# SalinityExpansion.net
KiCad netlist of a schematic drawn in EAGLE
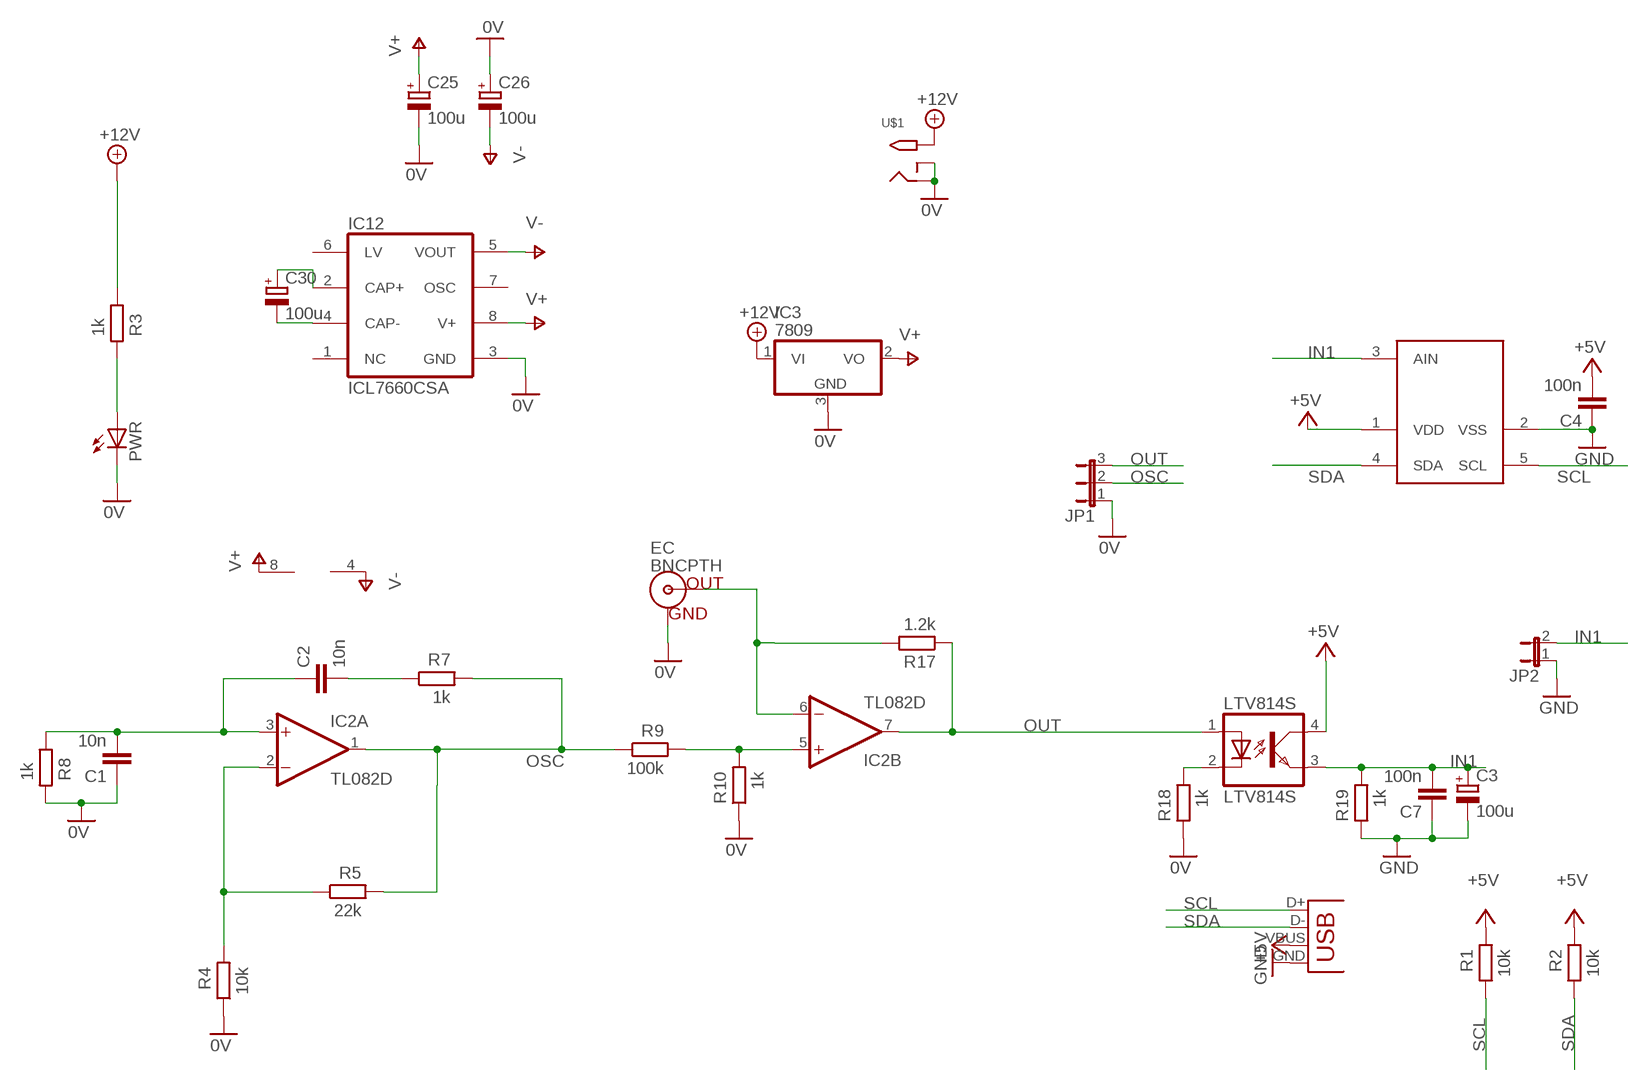
[diagram p0: schematic, sheet 1]

(export (version "E")
  (design (tool "Eeschema 10.0.6"))
  (components
    (comp (ref "C1")
      (value "10n")
      (footprint "eagle-import:C0805K")
      (libsource (lib "eagle-import") (part "C-EUC0805K"))
    )
    (comp (ref "C2")
      (value "10n")
      (footprint "eagle-import:C0805K")
      (libsource (lib "eagle-import") (part "C-EUC0805K"))
    )
    (comp (ref "C3")
      (value "100u")
      (footprint "eagle-import:PANASONIC_D")
      (libsource (lib "eagle-import") (part "CPOL-EUD"))
    )
    (comp (ref "C4")
      (value "100n")
      (footprint "eagle-import:C0805K")
      (libsource (lib "eagle-import") (part "C-EUC0805K"))
    )
    (comp (ref "C7")
      (value "100n")
      (footprint "eagle-import:C0805K")
      (libsource (lib "eagle-import") (part "C-EUC0805K"))
    )
    (comp (ref "C25")
      (value "100u")
      (footprint "eagle-import:PANASONIC_D")
      (libsource (lib "eagle-import") (part "CPOL-EUD"))
    )
    (comp (ref "C26")
      (value "100u")
      (footprint "eagle-import:PANASONIC_D")
      (libsource (lib "eagle-import") (part "CPOL-EUD"))
    )
    (comp (ref "C30")
      (value "100u")
      (footprint "eagle-import:PANASONIC_D")
      (libsource (lib "eagle-import") (part "CPOL-EUD"))
    )
    (comp (ref "EC")
      (value "BNCPTH")
      (footprint "eagle-import:BNC")
      (libsource (lib "eagle-import") (part "BNCPTH"))
    )
    (comp (ref "IC2")
      (value "TL082D")
      (footprint "eagle-import:SO08")
      (libsource (lib "eagle-import") (part "TL082D"))
    )
    (comp (ref "IC3")
      (value "7809")
      (footprint "eagle-import:TO252")
      (libsource (lib "eagle-import") (part "78DT05"))
    )
    (comp (ref "IC12")
      (value "ICL7660CSA")
      (footprint "eagle-import:SO08")
      (fields (field (name "MF") "MAXIM"))
      (libsource (lib "eagle-import") (part "ICL7660CSA"))
    )
    (comp (ref "JP1")
      (value "JP2E")
      (footprint "eagle-import:JP2")
      (libsource (lib "eagle-import") (part "JP2E"))
    )
    (comp (ref "JP2")
      (value "JP1E")
      (footprint "eagle-import:JP1")
      (libsource (lib "eagle-import") (part "JP1E"))
    )
    (comp (ref "LTV814S")
      (value "LTV814S")
      (footprint "eagle-import:SMD4")
      (libsource (lib "eagle-import") (part "LTV816S"))
    )
    (comp (ref "PWR")
      (value "LED3MM")
      (footprint "eagle-import:LED3MM")
      (libsource (lib "eagle-import") (part "LED3MM"))
    )
    (comp (ref "R1")
      (value "10k")
      (footprint "eagle-import:R0805")
      (libsource (lib "eagle-import") (part "R-EU_R0805"))
    )
    (comp (ref "R2")
      (value "10k")
      (footprint "eagle-import:R0805")
      (libsource (lib "eagle-import") (part "R-EU_R0805"))
    )
    (comp (ref "R3")
      (value "1k")
      (footprint "eagle-import:R0805")
      (libsource (lib "eagle-import") (part "R-EU_R0805"))
    )
    (comp (ref "R4")
      (value "10k")
      (footprint "eagle-import:R0805")
      (libsource (lib "eagle-import") (part "R-EU_R0805"))
    )
    (comp (ref "R5")
      (value "22k")
      (footprint "eagle-import:R0805")
      (libsource (lib "eagle-import") (part "R-EU_R0805"))
    )
    (comp (ref "R7")
      (value "1k")
      (footprint "eagle-import:R0805")
      (libsource (lib "eagle-import") (part "R-EU_R0805"))
    )
    (comp (ref "R8")
      (value "1k")
      (footprint "eagle-import:R0805")
      (libsource (lib "eagle-import") (part "R-EU_R0805"))
    )
    (comp (ref "R9")
      (value "100k")
      (footprint "eagle-import:R0805")
      (libsource (lib "eagle-import") (part "R-EU_R0805"))
    )
    (comp (ref "R10")
      (value "1k")
      (footprint "eagle-import:R0805")
      (libsource (lib "eagle-import") (part "R-EU_R0805"))
    )
    (comp (ref "R17")
      (value "1.2k")
      (footprint "eagle-import:R0805")
      (libsource (lib "eagle-import") (part "R-EU_R0805"))
    )
    (comp (ref "R18")
      (value "1k")
      (footprint "eagle-import:R0805")
      (libsource (lib "eagle-import") (part "R-EU_R0805"))
    )
    (comp (ref "R19")
      (value "1k")
      (footprint "eagle-import:R0805")
      (libsource (lib "eagle-import") (part "R-EU_R0805"))
    )
    (comp (ref "U$1")
      (value "2.1MMJACKTHM")
      (footprint "eagle-import:PJ-102A")
      (libsource (lib "eagle-import") (part "2.1MMJACKTHM"))
    )
    (comp (ref "U$2")
      (value "MCP3221")
      (footprint "eagle-import:SOT23-5")
      (libsource (lib "eagle-import") (part "MCP3221"))
    )
    (comp (ref "X5")
      (value "USBSMD")
      (footprint "eagle-import:USB-MINIB")
      (libsource (lib "eagle-import") (part "USBSMD"))
    )
  )
  (nets
    (net (code "1") (name "+5V") (class "Default")
      (node (ref "C4") (pin "2") (pinfunction "2_2") (pintype "passive"))
      (node (ref "LTV814S") (pin "4") (pinfunction "COL_4") (pintype "passive"))
      (node (ref "R1") (pin "2") (pinfunction "2_2") (pintype "passive"))
      (node (ref "R2") (pin "2") (pinfunction "2_2") (pintype "passive"))
      (node (ref "U$2") (pin "1") (pinfunction "VDD_1") (pintype "bidirectional"))
      (node (ref "X5") (pin "VBUS") (pinfunction "VBUS_VBUS") (pintype "bidirectional"))
    )
    (net (code "2") (name "+12V") (class "Default")
      (node (ref "IC3") (pin "1") (pinfunction "VI_1") (pintype "input"))
      (node (ref "R3") (pin "1") (pinfunction "1_1") (pintype "passive"))
      (node (ref "U$1") (pin "TIP") (pinfunction "TIP_TIP") (pintype "bidirectional"))
    )
    (net (code "3") (name "/IN1") (class "Default")
      (node (ref "C3") (pin "+") (pinfunction "+_+") (pintype "passive"))
      (node (ref "C7") (pin "2") (pinfunction "2_2") (pintype "passive"))
      (node (ref "JP2") (pin "2") (pinfunction "2_2") (pintype "passive"))
      (node (ref "LTV814S") (pin "3") (pinfunction "EMIT_3") (pintype "passive"))
      (node (ref "R19") (pin "2") (pinfunction "2_2") (pintype "passive"))
      (node (ref "U$2") (pin "3") (pinfunction "AIN_3") (pintype "bidirectional"))
    )
    (net (code "4") (name "/OSC") (class "Default")
      (node (ref "IC2") (pin "1") (pinfunction "OUT_1") (pintype "output"))
      (node (ref "JP1") (pin "2") (pinfunction "2_2") (pintype "passive"))
      (node (ref "R5") (pin "2") (pinfunction "2_2") (pintype "passive"))
      (node (ref "R7") (pin "2") (pinfunction "2_2") (pintype "passive"))
      (node (ref "R9") (pin "1") (pinfunction "1_1") (pintype "passive"))
    )
    (net (code "5") (name "/OUT") (class "Default")
      (node (ref "IC2") (pin "7") (pinfunction "OUT_7") (pintype "output"))
      (node (ref "JP1") (pin "3") (pinfunction "3_3") (pintype "passive"))
      (node (ref "LTV814S") (pin "1") (pinfunction "A_1") (pintype "passive"))
      (node (ref "R17") (pin "1") (pinfunction "1_1") (pintype "passive"))
    )
    (net (code "6") (name "/SCL") (class "Default")
      (node (ref "R1") (pin "1") (pinfunction "1_1") (pintype "passive"))
      (node (ref "U$2") (pin "5") (pinfunction "SCL_5") (pintype "bidirectional"))
      (node (ref "X5") (pin "D+") (pinfunction "D+_D+") (pintype "bidirectional"))
    )
    (net (code "7") (name "/SDA") (class "Default")
      (node (ref "R2") (pin "1") (pinfunction "1_1") (pintype "passive"))
      (node (ref "U$2") (pin "4") (pinfunction "SDA_4") (pintype "bidirectional"))
      (node (ref "X5") (pin "D-") (pinfunction "D-_D-") (pintype "bidirectional"))
    )
    (net (code "8") (name "0V") (class "Default")
      (node (ref "C1") (pin "1") (pinfunction "1_1") (pintype "passive"))
      (node (ref "C25") (pin "-") (pinfunction "-_-") (pintype "passive"))
      (node (ref "C26") (pin "+") (pinfunction "+_+") (pintype "passive"))
      (node (ref "EC") (pin "GND") (pinfunction "GND_GND") (pintype "bidirectional"))
      (node (ref "IC12") (pin "3") (pinfunction "GND_3") (pintype "power_in"))
      (node (ref "IC3") (pin "3") (pinfunction "GND_3") (pintype "passive"))
      (node (ref "JP1") (pin "1") (pinfunction "1_1") (pintype "passive"))
      (node (ref "PWR") (pin "K") (pinfunction "C_K") (pintype "passive"))
      (node (ref "R10") (pin "1") (pinfunction "1_1") (pintype "passive"))
      (node (ref "R18") (pin "1") (pinfunction "1_1") (pintype "passive"))
      (node (ref "R4") (pin "1") (pinfunction "1_1") (pintype "passive"))
      (node (ref "R8") (pin "2") (pinfunction "2_2") (pintype "passive"))
      (node (ref "U$1") (pin "RING") (pinfunction "RING_RING") (pintype "bidirectional"))
      (node (ref "U$1") (pin "RING_SW") (pinfunction "RING_SW_RING_SW") (pintype "bidirectional"))
    )
    (net (code "9") (name "GND") (class "Default")
      (node (ref "C3") (pin "-") (pinfunction "-_-") (pintype "passive"))
      (node (ref "C4") (pin "1") (pinfunction "1_1") (pintype "passive"))
      (node (ref "C7") (pin "1") (pinfunction "1_1") (pintype "passive"))
      (node (ref "JP2") (pin "1") (pinfunction "1_1") (pintype "passive"))
      (node (ref "R19") (pin "1") (pinfunction "1_1") (pintype "passive"))
      (node (ref "U$2") (pin "2") (pinfunction "VSS_2") (pintype "bidirectional"))
      (node (ref "X5") (pin "GND") (pinfunction "GND_GND") (pintype "bidirectional"))
    )
    (net (code "10") (name "Net-(C2-Pad2)") (class "Default")
      (node (ref "C2") (pin "2") (pinfunction "2_2") (pintype "passive"))
      (node (ref "R7") (pin "1") (pinfunction "1_1") (pintype "passive"))
    )
    (net (code "11") (name "Net-(EC-OUT)") (class "Default")
      (node (ref "EC") (pin "S") (pinfunction "OUT_S") (pintype "bidirectional"))
      (node (ref "IC2") (pin "6") (pinfunction "-IN_6") (pintype "input"))
      (node (ref "R17") (pin "2") (pinfunction "2_2") (pintype "passive"))
    )
    (net (code "12") (name "Net-(IC2A-+IN)") (class "Default")
      (node (ref "C1") (pin "2") (pinfunction "2_2") (pintype "passive"))
      (node (ref "C2") (pin "1") (pinfunction "1_1") (pintype "passive"))
      (node (ref "IC2") (pin "3") (pinfunction "+IN_3") (pintype "input"))
      (node (ref "R8") (pin "1") (pinfunction "1_1") (pintype "passive"))
    )
    (net (code "13") (name "Net-(IC2A--IN)") (class "Default")
      (node (ref "IC2") (pin "2") (pinfunction "-IN_2") (pintype "input"))
      (node (ref "R4") (pin "2") (pinfunction "2_2") (pintype "passive"))
      (node (ref "R5") (pin "1") (pinfunction "1_1") (pintype "passive"))
    )
    (net (code "14") (name "Net-(IC2B-+IN)") (class "Default")
      (node (ref "IC2") (pin "5") (pinfunction "+IN_5") (pintype "input"))
      (node (ref "R10") (pin "2") (pinfunction "2_2") (pintype "passive"))
      (node (ref "R9") (pin "2") (pinfunction "2_2") (pintype "passive"))
    )
    (net (code "15") (name "Net-(IC12-CAP+)") (class "Default")
      (node (ref "C30") (pin "+") (pinfunction "+_+") (pintype "passive"))
      (node (ref "IC12") (pin "2") (pinfunction "CAP+_2") (pintype "passive"))
    )
    (net (code "16") (name "Net-(IC12-CAP-)") (class "Default")
      (node (ref "C30") (pin "-") (pinfunction "-_-") (pintype "passive"))
      (node (ref "IC12") (pin "4") (pinfunction "CAP-_4") (pintype "passive"))
    )
    (net (code "17") (name "Net-(LTV814S-C)") (class "Default")
      (node (ref "LTV814S") (pin "2") (pinfunction "C_2") (pintype "passive"))
      (node (ref "R18") (pin "2") (pinfunction "2_2") (pintype "passive"))
    )
    (net (code "18") (name "Net-(PWR-PadA)") (class "Default")
      (node (ref "PWR") (pin "A") (pinfunction "A_A") (pintype "passive"))
      (node (ref "R3") (pin "2") (pinfunction "2_2") (pintype "passive"))
    )
    (net (code "19") (name "V+") (class "Default")
      (node (ref "C25") (pin "+") (pinfunction "+_+") (pintype "passive"))
      (node (ref "IC12") (pin "8") (pinfunction "V+_8") (pintype "power_in"))
      (node (ref "IC2") (pin "8") (pinfunction "V+_8") (pintype "power_in"))
      (node (ref "IC3") (pin "2") (pinfunction "VO_2") (pintype "passive"))
    )
    (net (code "20") (name "V-") (class "Default")
      (node (ref "C26") (pin "-") (pinfunction "-_-") (pintype "passive"))
      (node (ref "IC12") (pin "5") (pinfunction "VOUT_5") (pintype "output"))
      (node (ref "IC2") (pin "4") (pinfunction "V-_4") (pintype "power_in"))
    )
    (net (code "21") (name "unconnected-(IC12-LV-Pad6)") (class "Default")
      (node (ref "IC12") (pin "6") (pinfunction "LV_6") (pintype "passive"))
    )
    (net (code "22") (name "unconnected-(IC12-NC-Pad1)") (class "Default")
      (node (ref "IC12") (pin "1") (pinfunction "NC_1") (pintype "no_connect"))
    )
    (net (code "23") (name "unconnected-(IC12-OSC-Pad7)") (class "Default")
      (node (ref "IC12") (pin "7") (pinfunction "OSC_7") (pintype "output"))
    )
  )
)
